# schematics.net
KiCad netlist of a schematic drawn in EasyEDA
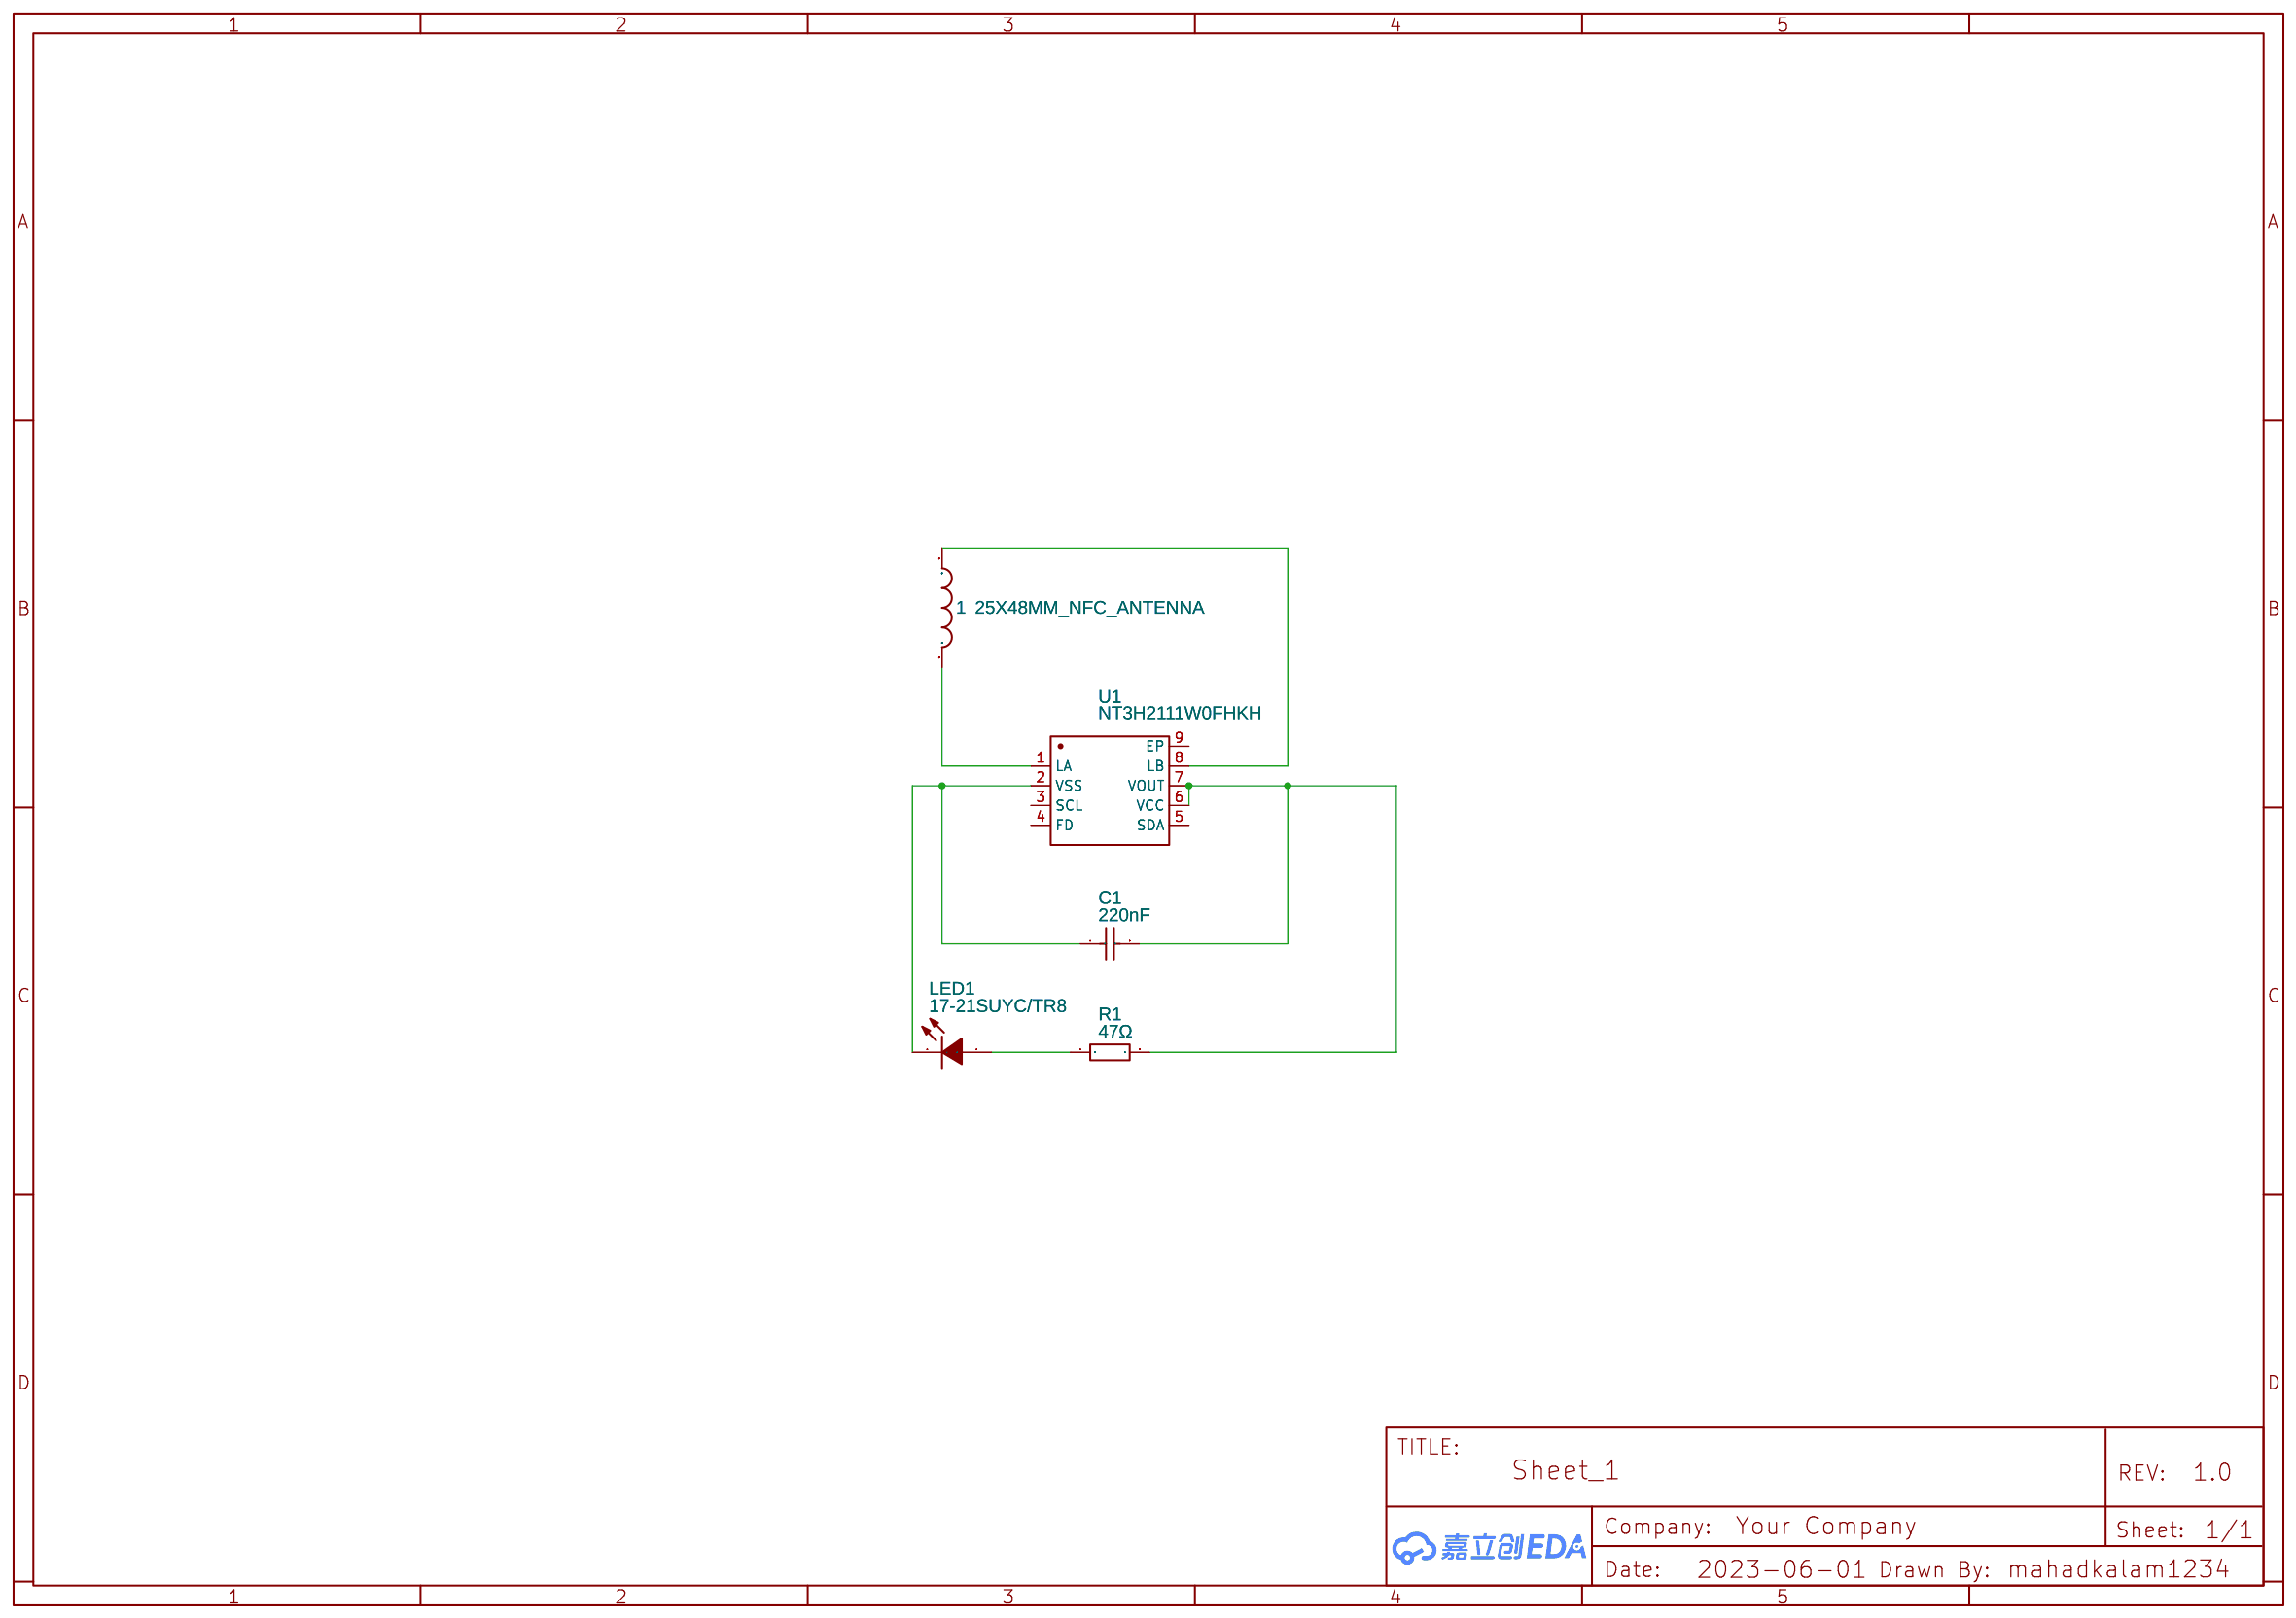
[diagram p0: schematic sheet]

(export (version "E")
  (design (tool "Eeschema 10.0.6"))
  (components
    (comp (ref "1") (value "25X48MM_NFC_ANTENNA") (libsource (lib "") (part "25X48MM_NFC_ANTENNA")))
    (comp (ref "C1")
      (value "220nF")
      (fields
        (field (name "Manufacturer Part") "CL10B224KA8NNNC")
        (field (name "Manufacturer") "SAMSUNG(三星)")
      )
      (libsource (lib "") (part "CL10B224KA8NNNC"))
    )
    (comp (ref "LED1")
      (value "17-21SUYC/TR8")
      (fields (field (name "Manufacturer Part") "KT-0805黄灯") (field (name "Manufacturer") "KENTO"))
      (libsource (lib "") (part "17-21SUYC/TR8"))
    )
    (comp (ref "R1")
      (value "47Ω")
      (fields
        (field (name "Manufacturer Part") "0603WAF470JT5E")
        (field (name "Manufacturer") "UNI-ROYAL(厚声)")
      )
      (libsource (lib "") (part "0603WAF470JT5E"))
    )
    (comp (ref "U1")
      (value "NT3H2111W0FHKH")
      (fields (field (name "Manufacturer") "NXP(恩智浦)"))
      (libsource (lib "") (part "NT3H2111W0FHKH"))
    )
  )
  (nets
    (net (code "1") (name "Net-(LED1-+)") (class "Default")
      (node (ref "LED1") (pin "1") (pinfunction "+_1") (pintype "unspecified"))
      (node (ref "R1") (pin "1") (pinfunction "1_1") (pintype "input"))
    )
    (net (code "2") (name "Net-(LED1--)") (class "Default")
      (node (ref "C1") (pin "1") (pinfunction "1_1") (pintype "input"))
      (node (ref "LED1") (pin "2") (pinfunction "-_2") (pintype "unspecified"))
      (node (ref "U1") (pin "2") (pinfunction "VSS_2") (pintype "unspecified"))
    )
    (net (code "3") (name "Net-(U1-LA)") (class "Default")
      (node (ref "1") (pin "P$2") (pinfunction "P$2_P$2") (pintype "bidirectional"))
      (node (ref "U1") (pin "1") (pinfunction "LA_1") (pintype "unspecified"))
    )
    (net (code "4") (name "Net-(U1-LB)") (class "Default")
      (node (ref "1") (pin "P$1") (pinfunction "P$1_P$1") (pintype "bidirectional"))
      (node (ref "U1") (pin "8") (pinfunction "LB_8") (pintype "unspecified"))
    )
    (net (code "5") (name "Net-(U1-VCC)") (class "Default")
      (node (ref "C1") (pin "2") (pinfunction "2_2") (pintype "input"))
      (node (ref "R1") (pin "2") (pinfunction "2_2") (pintype "input"))
      (node (ref "U1") (pin "6") (pinfunction "VCC_6") (pintype "unspecified"))
      (node (ref "U1") (pin "7") (pinfunction "VOUT_7") (pintype "unspecified"))
    )
    (net (code "6") (name "unconnected-(U1-EP-Pad9)") (class "Default")
      (node (ref "U1") (pin "9") (pinfunction "EP_9") (pintype "unspecified"))
    )
    (net (code "7") (name "unconnected-(U1-FD-Pad4)") (class "Default")
      (node (ref "U1") (pin "4") (pinfunction "FD_4") (pintype "unspecified"))
    )
    (net (code "8") (name "unconnected-(U1-SCL-Pad3)") (class "Default")
      (node (ref "U1") (pin "3") (pinfunction "SCL_3") (pintype "unspecified"))
    )
    (net (code "9") (name "unconnected-(U1-SDA-Pad5)") (class "Default")
      (node (ref "U1") (pin "5") (pinfunction "SDA_5") (pintype "unspecified"))
    )
  )
)
